# oblig.net
KiCad netlist of a schematic drawn in EAGLE
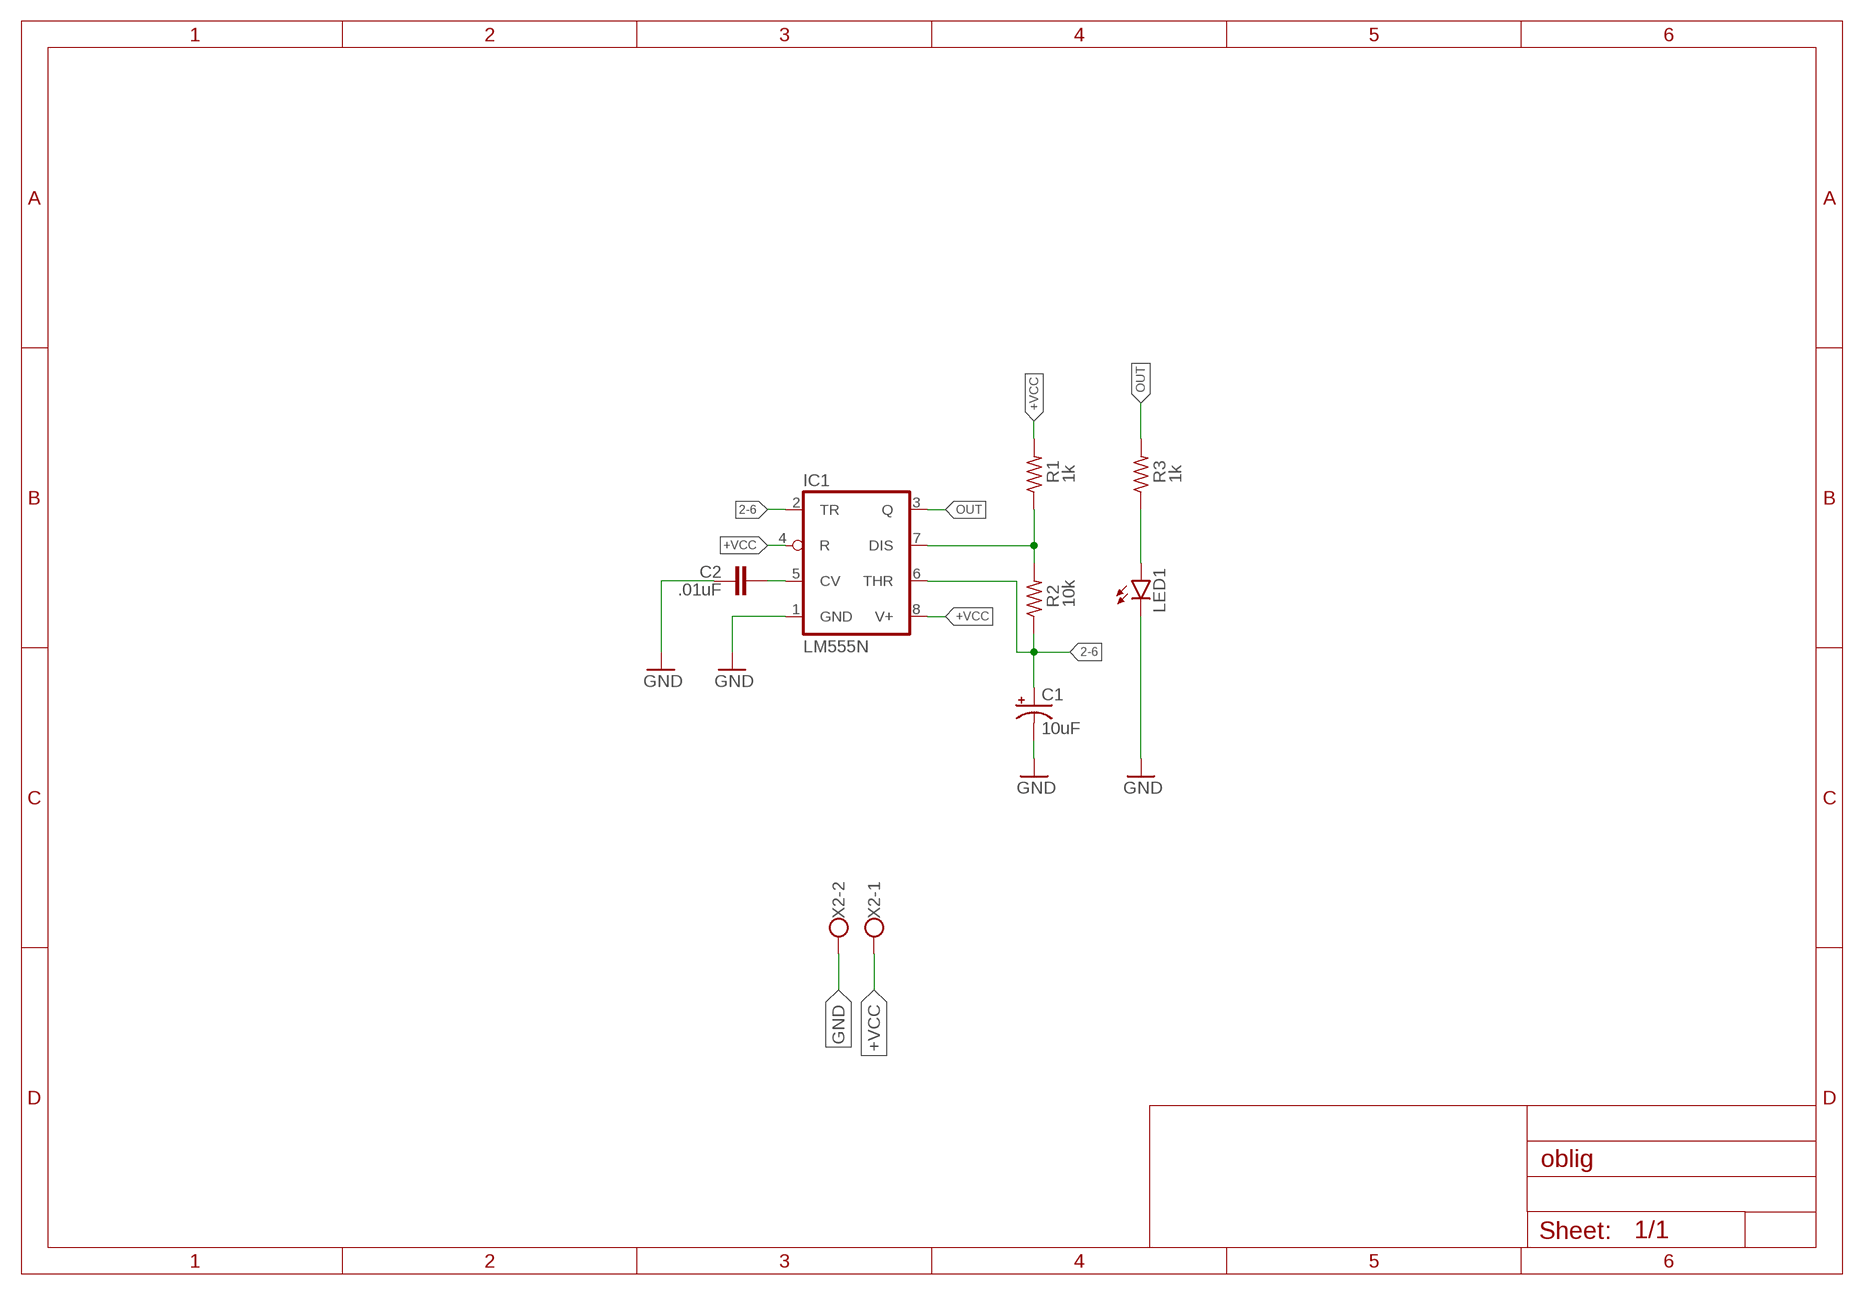
[diagram p0: schematic, sheet 1]

(export (version "E")
  (design (tool "Eeschema 10.0.6"))
  (components
    (comp (ref "C1")
      (value "10uF")
      (footprint "eagle-import:E2-5")
      (libsource (lib "eagle-import") (part "CPOL-USE2-5"))
    )
    (comp (ref "C2")
      (value ".01uF")
      (footprint "eagle-import:C050-024X044")
      (libsource (lib "eagle-import") (part "C-EU050-024X044"))
    )
    (comp (ref "IC1")
      (value "LM555N")
      (footprint "eagle-import:DIL08")
      (libsource (lib "eagle-import") (part "555NLM"))
    )
    (comp (ref "LED1")
      (value "LED5MM")
      (footprint "eagle-import:LED5MM")
      (libsource (lib "eagle-import") (part "LED5MM"))
    )
    (comp (ref "R1")
      (value "1k")
      (footprint "eagle-import:0207_10")
      (libsource (lib "eagle-import") (part "R-US_0207/10"))
    )
    (comp (ref "R2")
      (value "10k")
      (footprint "eagle-import:0207_10")
      (libsource (lib "eagle-import") (part "R-US_0207/10"))
    )
    (comp (ref "R3")
      (value "1k")
      (footprint "eagle-import:0207_10")
      (libsource (lib "eagle-import") (part "R-US_0207/10"))
    )
    (comp (ref "X2")
      (value "W237-102")
      (footprint "eagle-import:W237-102")
      (fields (field (name "MPN") "237-102"))
      (libsource (lib "eagle-import") (part "W237-102"))
    )
  )
  (nets
    (net (code "1") (name "+VCC") (class "Default")
      (node (ref "IC1") (pin "4") (pinfunction "R_4") (pintype "input"))
      (node (ref "IC1") (pin "8") (pinfunction "V+_8") (pintype "power_in"))
      (node (ref "R1") (pin "2") (pinfunction "2_2") (pintype "passive"))
      (node (ref "X2") (pin "1") (pinfunction "KL_1") (pintype "passive"))
    )
    (net (code "2") (name "2-6") (class "Default")
      (node (ref "C1") (pin "+") (pinfunction "+_+") (pintype "passive"))
      (node (ref "IC1") (pin "2") (pinfunction "TR_2") (pintype "input"))
      (node (ref "IC1") (pin "6") (pinfunction "THR_6") (pintype "input"))
      (node (ref "R2") (pin "1") (pinfunction "1_1") (pintype "passive"))
    )
    (net (code "3") (name "GND") (class "Default")
      (node (ref "C1") (pin "-") (pinfunction "-_-") (pintype "passive"))
      (node (ref "C2") (pin "1") (pinfunction "1_1") (pintype "passive"))
      (node (ref "IC1") (pin "1") (pinfunction "GND_1") (pintype "power_in"))
      (node (ref "LED1") (pin "K") (pinfunction "C_K") (pintype "passive"))
      (node (ref "X2") (pin "2") (pinfunction "KL_2") (pintype "passive"))
    )
    (net (code "4") (name "Net-(IC1-CV)") (class "Default")
      (node (ref "C2") (pin "2") (pinfunction "2_2") (pintype "passive"))
      (node (ref "IC1") (pin "5") (pinfunction "CV_5") (pintype "input"))
    )
    (net (code "5") (name "Net-(IC1-DIS)") (class "Default")
      (node (ref "IC1") (pin "7") (pinfunction "DIS_7") (pintype "input"))
      (node (ref "R1") (pin "1") (pinfunction "1_1") (pintype "passive"))
      (node (ref "R2") (pin "2") (pinfunction "2_2") (pintype "passive"))
    )
    (net (code "6") (name "Net-(LED1-PadA)") (class "Default")
      (node (ref "LED1") (pin "A") (pinfunction "A_A") (pintype "passive"))
      (node (ref "R3") (pin "1") (pinfunction "1_1") (pintype "passive"))
    )
    (net (code "7") (name "OUT") (class "Default")
      (node (ref "IC1") (pin "3") (pinfunction "Q_3") (pintype "output"))
      (node (ref "R3") (pin "2") (pinfunction "2_2") (pintype "passive"))
    )
  )
)
